# SH2_-_CONNECTORS.net
KiCad netlist of a schematic drawn in Altium Designer
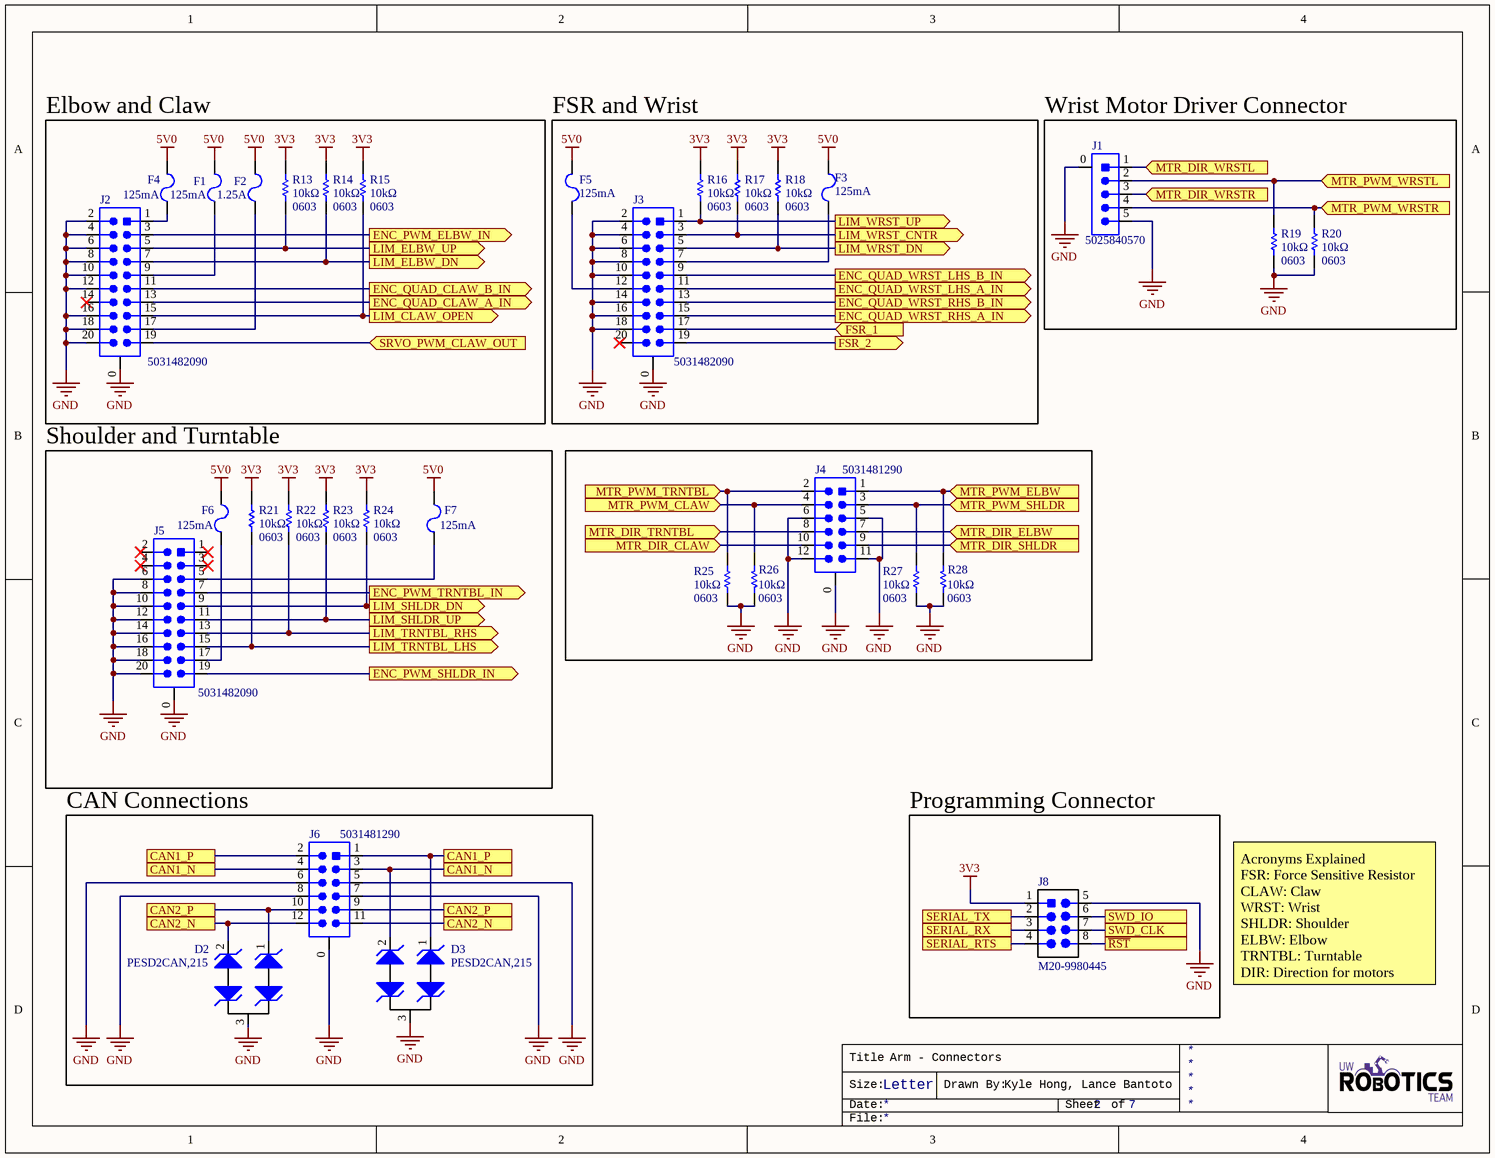
[diagram p0: SH2 - CONNECTORS.SchDoc]

(export (version "E")
  (design (tool "Eeschema 10.0.6"))
  (components
    (comp (ref "D2")
      (value "TVS_DIODE_CAN")
      (footprint "TVS_DIODE_CAN")
      (description "TVS DIODE 24V 41V SOT323-3")
      (fields (field (name "MANUFACTURER PART NUMBER 1") "PESD2CAN,215"))
      (libsource (lib "UWRT_Schematic_Library_2020") (part "TVS_DIODE_CAN"))
    )
    (comp (ref "D3")
      (value "TVS_DIODE_CAN")
      (footprint "TVS_DIODE_CAN")
      (description "TVS DIODE 24V 41V SOT323-3")
      (fields (field (name "MANUFACTURER PART NUMBER 1") "PESD2CAN,215"))
      (libsource (lib "UWRT_Schematic_Library_2020") (part "TVS_DIODE_CAN"))
    )
    (comp (ref "F1")
      (value "FUSE_125mA_1206")
      (footprint "FUSE_1206")
      (description "FUSE SMD 125mA 125V")
      (fields (field (name "CURRENT RATING") "125mA"))
      (libsource (lib "UWRT_Schematic_Library_2020") (part "FUSE_125mA_1206"))
    )
    (comp (ref "F2")
      (value "FUSE_1.25A_1206")
      (footprint "FUSE_1206")
      (description "FUSE SMD 1.25A 63V")
      (fields (field (name "CURRENT RATING") "1.25A"))
      (libsource (lib "UWRT_Schematic_Library_2020") (part "FUSE_1.25A_1206"))
    )
    (comp (ref "F3")
      (value "FUSE_125mA_1206")
      (footprint "FUSE_1206")
      (description "FUSE SMD 125mA 125V")
      (fields (field (name "CURRENT RATING") "125mA"))
      (libsource (lib "UWRT_Schematic_Library_2020") (part "FUSE_125mA_1206"))
    )
    (comp (ref "F4")
      (value "FUSE_125mA_1206")
      (footprint "FUSE_1206")
      (description "FUSE SMD 125mA 125V")
      (fields (field (name "CURRENT RATING") "125mA"))
      (libsource (lib "UWRT_Schematic_Library_2020") (part "FUSE_125mA_1206"))
    )
    (comp (ref "F5")
      (value "FUSE_125mA_1206")
      (footprint "FUSE_1206")
      (description "FUSE SMD 125mA 125V")
      (fields (field (name "CURRENT RATING") "125mA"))
      (libsource (lib "") (part "FUSE_125mA_1206_1"))
    )
    (comp (ref "F6")
      (value "FUSE_125mA_1206")
      (footprint "FUSE_1206")
      (description "FUSE SMD 125mA 125V")
      (fields (field (name "CURRENT RATING") "125mA"))
      (libsource (lib "UWRT_Schematic_Library_2020") (part "FUSE_125mA_1206"))
    )
    (comp (ref "F7")
      (value "FUSE_125mA_1206")
      (footprint "FUSE_1206")
      (description "FUSE SMD 125mA 125V")
      (fields (field (name "CURRENT RATING") "125mA"))
      (libsource (lib "UWRT_Schematic_Library_2020") (part "FUSE_125mA_1206"))
    )
    (comp (ref "J1")
      (value "CON_5M_SM_VT")
      (footprint "MOLEX-5025840570")
      (description "CONN HEADER SMD VERTICAL 1.5MM PITCH")
      (fields (field (name "MANUFACTURER PART NUMBER 1") "5025840570"))
      (libsource (lib "UWRT_Schematic_Library_2020") (part "CON_5M_SM_VT"))
    )
    (comp (ref "J2")
      (value "CON_10x2M_SM_RA")
      (footprint "MOLEX-5031482090")
      (description "CONN HEADER SMD RIGHT ANGLE 1.5MM PITCH")
      (fields (field (name "MANUFACTURER PART NUMBER 1") "5031482090"))
      (libsource (lib "UWRT_Schematic_Library_2020") (part "CON_10x2M_SM_RA"))
    )
    (comp (ref "J3")
      (value "CON_10x2M_SM_RA")
      (footprint "MOLEX-5031482090")
      (description "CONN HEADER SMD RIGHT ANGLE 1.5MM PITCH")
      (fields (field (name "MANUFACTURER PART NUMBER 1") "5031482090"))
      (libsource (lib "UWRT_Schematic_Library_2020") (part "CON_10x2M_SM_RA"))
    )
    (comp (ref "J4")
      (value "CON_6x2M_SM_RA")
      (footprint "MOLEX-5031481290")
      (description "CONN HEADER SMD RIGHT ANGLE 1.5MM PITCH")
      (fields (field (name "MANUFACTURER PART NUMBER 1") "5031481290"))
      (libsource (lib "UWRT_Schematic_Library_2020") (part "CON_6x2M_SM_RA"))
    )
    (comp (ref "J5")
      (value "CON_10x2M_SM_RA")
      (footprint "MOLEX-5031482090")
      (description "CONN HEADER SMD RIGHT ANGLE 1.5MM PITCH")
      (fields (field (name "MANUFACTURER PART NUMBER 1") "5031482090"))
      (libsource (lib "UWRT_Schematic_Library_2020") (part "CON_10x2M_SM_RA"))
    )
    (comp (ref "J6")
      (value "CON_6x2M_SM_RA")
      (footprint "MOLEX-5031481290")
      (description "CONN HEADER SMD RIGHT ANGLE 1.5MM PITCH")
      (fields (field (name "MANUFACTURER PART NUMBER 1") "5031481290"))
      (libsource (lib "UWRT_Schematic_Library_2020") (part "CON_6x2M_SM_RA"))
    )
    (comp (ref "J8")
      (value "HEADER 4X2")
      (footprint "HEADER_2X4")
      (description "CONN HEADER VERT 8POS 2.54MM")
      (fields (field (name "MANUFACTURER PART NUMBER 1") "M20-9980445"))
      (libsource (lib "UWRT_Schematic_Library_2020") (part "HEADER 4X2"))
    )
    (comp (ref "R13")
      (value "10kΩ")
      (footprint "RESC0603(1608)_N")
      (description "RES SMD 10K OHM 5% 1/10W 0603")
      (fields
        (field (name "TOLERANCE") "5%")
        (field (name "CASE CODE (IMPERIAL)") "0603")
        (field (name "Comment") "RES_10kΩ_0603")
      )
      (libsource (lib "UWRT_Schematic_Library_2020") (part "RES_10kΩ_0603"))
    )
    (comp (ref "R14")
      (value "10kΩ")
      (footprint "RESC0603(1608)_N")
      (description "RES SMD 10K OHM 5% 1/10W 0603")
      (fields
        (field (name "TOLERANCE") "5%")
        (field (name "CASE CODE (IMPERIAL)") "0603")
        (field (name "Comment") "RES_10kΩ_0603")
      )
      (libsource (lib "UWRT_Schematic_Library_2020") (part "RES_10kΩ_0603"))
    )
    (comp (ref "R15")
      (value "10kΩ")
      (footprint "RESC0603(1608)_N")
      (description "RES SMD 10K OHM 5% 1/10W 0603")
      (fields
        (field (name "TOLERANCE") "5%")
        (field (name "CASE CODE (IMPERIAL)") "0603")
        (field (name "Comment") "RES_10kΩ_0603")
      )
      (libsource (lib "UWRT_Schematic_Library_2020") (part "RES_10kΩ_0603"))
    )
    (comp (ref "R16")
      (value "10kΩ")
      (footprint "RESC0603(1608)_N")
      (description "RES SMD 10K OHM 5% 1/10W 0603")
      (fields
        (field (name "TOLERANCE") "5%")
        (field (name "CASE CODE (IMPERIAL)") "0603")
        (field (name "Comment") "RES_10kΩ_0603")
      )
      (libsource (lib "UWRT_Schematic_Library_2020") (part "RES_10kΩ_0603"))
    )
    (comp (ref "R17")
      (value "10kΩ")
      (footprint "RESC0603(1608)_N")
      (description "RES SMD 10K OHM 5% 1/10W 0603")
      (fields
        (field (name "TOLERANCE") "5%")
        (field (name "CASE CODE (IMPERIAL)") "0603")
        (field (name "Comment") "RES_10kΩ_0603")
      )
      (libsource (lib "UWRT_Schematic_Library_2020") (part "RES_10kΩ_0603"))
    )
    (comp (ref "R18")
      (value "10kΩ")
      (footprint "RESC0603(1608)_N")
      (description "RES SMD 10K OHM 5% 1/10W 0603")
      (fields
        (field (name "TOLERANCE") "5%")
        (field (name "CASE CODE (IMPERIAL)") "0603")
        (field (name "Comment") "RES_10kΩ_0603")
      )
      (libsource (lib "UWRT_Schematic_Library_2020") (part "RES_10kΩ_0603"))
    )
    (comp (ref "R19")
      (value "10kΩ")
      (footprint "RESC0603(1608)_N")
      (description "RES SMD 10K OHM 5% 1/10W 0603")
      (fields
        (field (name "TOLERANCE") "5%")
        (field (name "CASE CODE (IMPERIAL)") "0603")
        (field (name "Comment") "RES_10kΩ_0603")
      )
      (libsource (lib "UWRT_Schematic_Library_2020") (part "RES_10kΩ_0603"))
    )
    (comp (ref "R20")
      (value "10kΩ")
      (footprint "RESC0603(1608)_N")
      (description "RES SMD 10K OHM 5% 1/10W 0603")
      (fields
        (field (name "TOLERANCE") "5%")
        (field (name "CASE CODE (IMPERIAL)") "0603")
        (field (name "Comment") "RES_10kΩ_0603")
      )
      (libsource (lib "UWRT_Schematic_Library_2020") (part "RES_10kΩ_0603"))
    )
    (comp (ref "R21")
      (value "10kΩ")
      (footprint "RESC0603(1608)_N")
      (description "RES SMD 10K OHM 5% 1/10W 0603")
      (fields
        (field (name "TOLERANCE") "5%")
        (field (name "CASE CODE (IMPERIAL)") "0603")
        (field (name "Comment") "RES_10kΩ_0603")
      )
      (libsource (lib "UWRT_Schematic_Library_2020") (part "RES_10kΩ_0603"))
    )
    (comp (ref "R22")
      (value "10kΩ")
      (footprint "RESC0603(1608)_N")
      (description "RES SMD 10K OHM 5% 1/10W 0603")
      (fields
        (field (name "TOLERANCE") "5%")
        (field (name "CASE CODE (IMPERIAL)") "0603")
        (field (name "Comment") "RES_10kΩ_0603")
      )
      (libsource (lib "UWRT_Schematic_Library_2020") (part "RES_10kΩ_0603"))
    )
    (comp (ref "R23")
      (value "10kΩ")
      (footprint "RESC0603(1608)_N")
      (description "RES SMD 10K OHM 5% 1/10W 0603")
      (fields
        (field (name "TOLERANCE") "5%")
        (field (name "CASE CODE (IMPERIAL)") "0603")
        (field (name "Comment") "RES_10kΩ_0603")
      )
      (libsource (lib "UWRT_Schematic_Library_2020") (part "RES_10kΩ_0603"))
    )
    (comp (ref "R24")
      (value "10kΩ")
      (footprint "RESC0603(1608)_N")
      (description "RES SMD 10K OHM 5% 1/10W 0603")
      (fields
        (field (name "TOLERANCE") "5%")
        (field (name "CASE CODE (IMPERIAL)") "0603")
        (field (name "Comment") "RES_10kΩ_0603")
      )
      (libsource (lib "UWRT_Schematic_Library_2020") (part "RES_10kΩ_0603"))
    )
    (comp (ref "R25")
      (value "10kΩ")
      (footprint "RESC0603(1608)_N")
      (description "RES SMD 10K OHM 5% 1/10W 0603")
      (fields
        (field (name "TOLERANCE") "5%")
        (field (name "CASE CODE (IMPERIAL)") "0603")
        (field (name "Comment") "RES_10kΩ_0603")
      )
      (libsource (lib "UWRT_Schematic_Library_2020") (part "RES_10kΩ_0603"))
    )
    (comp (ref "R26")
      (value "10kΩ")
      (footprint "RESC0603(1608)_N")
      (description "RES SMD 10K OHM 5% 1/10W 0603")
      (fields
        (field (name "TOLERANCE") "5%")
        (field (name "CASE CODE (IMPERIAL)") "0603")
        (field (name "Comment") "RES_10kΩ_0603")
      )
      (libsource (lib "UWRT_Schematic_Library_2020") (part "RES_10kΩ_0603"))
    )
    (comp (ref "R27")
      (value "10kΩ")
      (footprint "RESC0603(1608)_N")
      (description "RES SMD 10K OHM 5% 1/10W 0603")
      (fields
        (field (name "TOLERANCE") "5%")
        (field (name "CASE CODE (IMPERIAL)") "0603")
        (field (name "Comment") "RES_10kΩ_0603")
      )
      (libsource (lib "UWRT_Schematic_Library_2020") (part "RES_10kΩ_0603"))
    )
    (comp (ref "R28")
      (value "10kΩ")
      (footprint "RESC0603(1608)_N")
      (description "RES SMD 10K OHM 5% 1/10W 0603")
      (fields
        (field (name "TOLERANCE") "5%")
        (field (name "CASE CODE (IMPERIAL)") "0603")
        (field (name "Comment") "RES_10kΩ_0603")
      )
      (libsource (lib "UWRT_Schematic_Library_2020") (part "RES_10kΩ_0603"))
    )
  )
  (nets
    (net (code "1") (name "/CAN1_N") (class "Default")
      (node (ref "D3") (pin "2") (pinfunction "2_2") (pintype "passive"))
      (node (ref "J6") (pin "3") (pinfunction "3_3") (pintype "passive"))
      (node (ref "J6") (pin "4") (pinfunction "4_4") (pintype "passive"))
    )
    (net (code "2") (name "/CAN1_P") (class "Default")
      (node (ref "D3") (pin "1") (pinfunction "1_1") (pintype "passive"))
      (node (ref "J6") (pin "1") (pinfunction "1_1") (pintype "passive"))
      (node (ref "J6") (pin "2") (pinfunction "2_2") (pintype "passive"))
    )
    (net (code "3") (name "/CAN2_N") (class "Default")
      (node (ref "D2") (pin "2") (pinfunction "2_2") (pintype "passive"))
      (node (ref "J6") (pin "11") (pinfunction "11_11") (pintype "passive"))
      (node (ref "J6") (pin "12") (pinfunction "12_12") (pintype "passive"))
    )
    (net (code "4") (name "/CAN2_P") (class "Default")
      (node (ref "D2") (pin "1") (pinfunction "1_1") (pintype "passive"))
      (node (ref "J6") (pin "10") (pinfunction "10_10") (pintype "passive"))
      (node (ref "J6") (pin "9") (pinfunction "9_9") (pintype "passive"))
    )
    (net (code "5") (name "/ENC_PWM_ELBW_IN") (class "Default")
      (node (ref "J2") (pin "3") (pinfunction "3_3") (pintype "passive"))
    )
    (net (code "6") (name "/ENC_PWM_SHLDR_IN") (class "Default")
      (node (ref "J5") (pin "19") (pinfunction "19_19") (pintype "passive"))
    )
    (net (code "7") (name "/ENC_PWM_TRNTBL_IN") (class "Default")
      (node (ref "J5") (pin "7") (pinfunction "7_7") (pintype "passive"))
    )
    (net (code "8") (name "/ENC_QUAD_CLAW_A_IN") (class "Default")
      (node (ref "J2") (pin "13") (pinfunction "13_13") (pintype "passive"))
    )
    (net (code "9") (name "/ENC_QUAD_CLAW_B_IN") (class "Default")
      (node (ref "J2") (pin "11") (pinfunction "11_11") (pintype "passive"))
    )
    (net (code "10") (name "/ENC_QUAD_WRST_LHS_A_IN") (class "Default")
      (node (ref "J3") (pin "11") (pinfunction "11_11") (pintype "passive"))
    )
    (net (code "11") (name "/ENC_QUAD_WRST_LHS_B_IN") (class "Default")
      (node (ref "J3") (pin "9") (pinfunction "9_9") (pintype "passive"))
    )
    (net (code "12") (name "/ENC_QUAD_WRST_RHS_A_IN") (class "Default")
      (node (ref "J3") (pin "15") (pinfunction "15_15") (pintype "passive"))
    )
    (net (code "13") (name "/ENC_QUAD_WRST_RHS_B_IN") (class "Default")
      (node (ref "J3") (pin "13") (pinfunction "13_13") (pintype "passive"))
    )
    (net (code "14") (name "/FSR_1") (class "Default")
      (node (ref "J3") (pin "17") (pinfunction "17_17") (pintype "passive"))
    )
    (net (code "15") (name "/FSR_2") (class "Default")
      (node (ref "J3") (pin "19") (pinfunction "19_19") (pintype "passive"))
    )
    (net (code "16") (name "/LIM_CLAW_OPEN") (class "Default")
      (node (ref "J2") (pin "15") (pinfunction "15_15") (pintype "passive"))
      (node (ref "R15") (pin "1") (pinfunction "1_1") (pintype "passive"))
    )
    (net (code "17") (name "/LIM_ELBW_DN") (class "Default")
      (node (ref "J2") (pin "7") (pinfunction "7_7") (pintype "passive"))
      (node (ref "R14") (pin "1") (pinfunction "1_1") (pintype "passive"))
    )
    (net (code "18") (name "/LIM_ELBW_UP") (class "Default")
      (node (ref "J2") (pin "5") (pinfunction "5_5") (pintype "passive"))
      (node (ref "R13") (pin "1") (pinfunction "1_1") (pintype "passive"))
    )
    (net (code "19") (name "/LIM_SHLDR_DN") (class "Default")
      (node (ref "J5") (pin "9") (pinfunction "9_9") (pintype "passive"))
      (node (ref "R24") (pin "1") (pinfunction "1_1") (pintype "passive"))
    )
    (net (code "20") (name "/LIM_SHLDR_UP") (class "Default")
      (node (ref "J5") (pin "11") (pinfunction "11_11") (pintype "passive"))
      (node (ref "R23") (pin "1") (pinfunction "1_1") (pintype "passive"))
    )
    (net (code "21") (name "/LIM_TRNTBL_LHS") (class "Default")
      (node (ref "J5") (pin "15") (pinfunction "15_15") (pintype "passive"))
      (node (ref "R21") (pin "1") (pinfunction "1_1") (pintype "passive"))
    )
    (net (code "22") (name "/LIM_TRNTBL_RHS") (class "Default")
      (node (ref "J5") (pin "13") (pinfunction "13_13") (pintype "passive"))
      (node (ref "R22") (pin "1") (pinfunction "1_1") (pintype "passive"))
    )
    (net (code "23") (name "/LIM_WRST_CNTR") (class "Default")
      (node (ref "J3") (pin "3") (pinfunction "3_3") (pintype "passive"))
      (node (ref "R17") (pin "1") (pinfunction "1_1") (pintype "passive"))
    )
    (net (code "24") (name "/LIM_WRST_DN") (class "Default")
      (node (ref "J3") (pin "5") (pinfunction "5_5") (pintype "passive"))
      (node (ref "R18") (pin "1") (pinfunction "1_1") (pintype "passive"))
    )
    (net (code "25") (name "/LIM_WRST_UP") (class "Default")
      (node (ref "J3") (pin "1") (pinfunction "1_1") (pintype "passive"))
      (node (ref "R16") (pin "1") (pinfunction "1_1") (pintype "passive"))
    )
    (net (code "26") (name "/MTR_DIR_CLAW") (class "Default")
      (node (ref "J4") (pin "10") (pinfunction "10_10") (pintype "passive"))
    )
    (net (code "27") (name "/MTR_DIR_ELBW") (class "Default")
      (node (ref "J4") (pin "7") (pinfunction "7_7") (pintype "passive"))
    )
    (net (code "28") (name "/MTR_DIR_SHLDR") (class "Default")
      (node (ref "J4") (pin "9") (pinfunction "9_9") (pintype "passive"))
    )
    (net (code "29") (name "/MTR_DIR_TRNTBL") (class "Default")
      (node (ref "J4") (pin "8") (pinfunction "8_8") (pintype "passive"))
    )
    (net (code "30") (name "/MTR_DIR_WRSTL") (class "Default")
      (node (ref "J1") (pin "1") (pinfunction "1_1") (pintype "passive"))
    )
    (net (code "31") (name "/MTR_DIR_WRSTR") (class "Default")
      (node (ref "J1") (pin "3") (pinfunction "3_3") (pintype "passive"))
    )
    (net (code "32") (name "/MTR_PWM_CLAW") (class "Default")
      (node (ref "J4") (pin "4") (pinfunction "4_4") (pintype "passive"))
      (node (ref "R26") (pin "2") (pinfunction "2_2") (pintype "passive"))
    )
    (net (code "33") (name "/MTR_PWM_ELBW") (class "Default")
      (node (ref "J4") (pin "1") (pinfunction "1_1") (pintype "passive"))
      (node (ref "R28") (pin "2") (pinfunction "2_2") (pintype "passive"))
    )
    (net (code "34") (name "/MTR_PWM_SHLDR") (class "Default")
      (node (ref "J4") (pin "3") (pinfunction "3_3") (pintype "passive"))
      (node (ref "R27") (pin "2") (pinfunction "2_2") (pintype "passive"))
    )
    (net (code "35") (name "/MTR_PWM_TRNTBL") (class "Default")
      (node (ref "J4") (pin "2") (pinfunction "2_2") (pintype "passive"))
      (node (ref "R25") (pin "2") (pinfunction "2_2") (pintype "passive"))
    )
    (net (code "36") (name "/MTR_PWM_WRSTL") (class "Default")
      (node (ref "J1") (pin "2") (pinfunction "2_2") (pintype "passive"))
      (node (ref "R19") (pin "2") (pinfunction "2_2") (pintype "passive"))
    )
    (net (code "37") (name "/MTR_PWM_WRSTR") (class "Default")
      (node (ref "J1") (pin "4") (pinfunction "4_4") (pintype "passive"))
      (node (ref "R20") (pin "2") (pinfunction "2_2") (pintype "passive"))
    )
    (net (code "38") (name "/SERIAL_RTS") (class "Default")
      (node (ref "J8") (pin "4") (pinfunction "4_4") (pintype "passive"))
    )
    (net (code "39") (name "/SERIAL_RX") (class "Default")
      (node (ref "J8") (pin "3") (pinfunction "3_3") (pintype "passive"))
    )
    (net (code "40") (name "/SERIAL_TX") (class "Default")
      (node (ref "J8") (pin "2") (pinfunction "2_2") (pintype "passive"))
    )
    (net (code "41") (name "/SRVO_PWM_CLAW_OUT") (class "Default")
      (node (ref "J2") (pin "19") (pinfunction "19_19") (pintype "passive"))
    )
    (net (code "42") (name "/SWD_CLK") (class "Default")
      (node (ref "J8") (pin "7") (pinfunction "3_7") (pintype "passive"))
    )
    (net (code "43") (name "/SWD_IO") (class "Default")
      (node (ref "J8") (pin "6") (pinfunction "2_6") (pintype "passive"))
    )
    (net (code "44") (name "/~{RST}") (class "Default")
      (node (ref "J8") (pin "8") (pinfunction "4_8") (pintype "passive"))
    )
    (net (code "45") (name "3V3") (class "Default")
      (node (ref "J8") (pin "1") (pinfunction "VCC_1") (pintype "passive"))
      (node (ref "R13") (pin "2") (pinfunction "2_2") (pintype "passive"))
      (node (ref "R14") (pin "2") (pinfunction "2_2") (pintype "passive"))
      (node (ref "R15") (pin "2") (pinfunction "2_2") (pintype "passive"))
      (node (ref "R16") (pin "2") (pinfunction "2_2") (pintype "passive"))
      (node (ref "R17") (pin "2") (pinfunction "2_2") (pintype "passive"))
      (node (ref "R18") (pin "2") (pinfunction "2_2") (pintype "passive"))
      (node (ref "R21") (pin "2") (pinfunction "2_2") (pintype "passive"))
      (node (ref "R22") (pin "2") (pinfunction "2_2") (pintype "passive"))
      (node (ref "R23") (pin "2") (pinfunction "2_2") (pintype "passive"))
      (node (ref "R24") (pin "2") (pinfunction "2_2") (pintype "passive"))
    )
    (net (code "46") (name "5V0") (class "Default")
      (node (ref "F1") (pin "2") (pinfunction "2_2") (pintype "passive"))
      (node (ref "F2") (pin "2") (pinfunction "2_2") (pintype "passive"))
      (node (ref "F3") (pin "2") (pinfunction "2_2") (pintype "passive"))
      (node (ref "F4") (pin "2") (pinfunction "2_2") (pintype "passive"))
      (node (ref "F5") (pin "2") (pinfunction "2_2") (pintype "passive"))
      (node (ref "F6") (pin "2") (pinfunction "2_2") (pintype "passive"))
      (node (ref "F7") (pin "2") (pinfunction "2_2") (pintype "passive"))
    )
    (net (code "47") (name "GND") (class "Default")
      (node (ref "D2") (pin "3") (pinfunction "3_3") (pintype "passive"))
      (node (ref "D3") (pin "3") (pinfunction "3_3") (pintype "passive"))
      (node (ref "J1") (pin "0") (pinfunction "0_0") (pintype "passive"))
      (node (ref "J1") (pin "5") (pinfunction "5_5") (pintype "passive"))
      (node (ref "J2") (pin "0") (pinfunction "0_0") (pintype "passive"))
      (node (ref "J2") (pin "10") (pinfunction "10_10") (pintype "passive"))
      (node (ref "J2") (pin "12") (pinfunction "12_12") (pintype "passive"))
      (node (ref "J2") (pin "16") (pinfunction "16_16") (pintype "passive"))
      (node (ref "J2") (pin "18") (pinfunction "18_18") (pintype "passive"))
      (node (ref "J2") (pin "2") (pinfunction "2_2") (pintype "passive"))
      (node (ref "J2") (pin "20") (pinfunction "20_20") (pintype "passive"))
      (node (ref "J2") (pin "4") (pinfunction "4_4") (pintype "passive"))
      (node (ref "J2") (pin "6") (pinfunction "6_6") (pintype "passive"))
      (node (ref "J2") (pin "8") (pinfunction "8_8") (pintype "passive"))
      (node (ref "J3") (pin "0") (pinfunction "0_0") (pintype "passive"))
      (node (ref "J3") (pin "10") (pinfunction "10_10") (pintype "passive"))
      (node (ref "J3") (pin "14") (pinfunction "14_14") (pintype "passive"))
      (node (ref "J3") (pin "16") (pinfunction "16_16") (pintype "passive"))
      (node (ref "J3") (pin "18") (pinfunction "18_18") (pintype "passive"))
      (node (ref "J3") (pin "2") (pinfunction "2_2") (pintype "passive"))
      (node (ref "J3") (pin "4") (pinfunction "4_4") (pintype "passive"))
      (node (ref "J3") (pin "6") (pinfunction "6_6") (pintype "passive"))
      (node (ref "J3") (pin "8") (pinfunction "8_8") (pintype "passive"))
      (node (ref "J4") (pin "0") (pinfunction "0_0") (pintype "passive"))
      (node (ref "J4") (pin "11") (pinfunction "11_11") (pintype "passive"))
      (node (ref "J4") (pin "12") (pinfunction "12_12") (pintype "passive"))
      (node (ref "J4") (pin "5") (pinfunction "5_5") (pintype "passive"))
      (node (ref "J4") (pin "6") (pinfunction "6_6") (pintype "passive"))
      (node (ref "J5") (pin "0") (pinfunction "0_0") (pintype "passive"))
      (node (ref "J5") (pin "10") (pinfunction "10_10") (pintype "passive"))
      (node (ref "J5") (pin "12") (pinfunction "12_12") (pintype "passive"))
      (node (ref "J5") (pin "14") (pinfunction "14_14") (pintype "passive"))
      (node (ref "J5") (pin "16") (pinfunction "16_16") (pintype "passive"))
      (node (ref "J5") (pin "18") (pinfunction "18_18") (pintype "passive"))
      (node (ref "J5") (pin "20") (pinfunction "20_20") (pintype "passive"))
      (node (ref "J5") (pin "6") (pinfunction "6_6") (pintype "passive"))
      (node (ref "J5") (pin "8") (pinfunction "8_8") (pintype "passive"))
      (node (ref "J6") (pin "0") (pinfunction "0_0") (pintype "passive"))
      (node (ref "J6") (pin "5") (pinfunction "5_5") (pintype "passive"))
      (node (ref "J6") (pin "6") (pinfunction "6_6") (pintype "passive"))
      (node (ref "J6") (pin "7") (pinfunction "7_7") (pintype "passive"))
      (node (ref "J6") (pin "8") (pinfunction "8_8") (pintype "passive"))
      (node (ref "J8") (pin "5") (pinfunction "GND_5") (pintype "passive"))
      (node (ref "R19") (pin "1") (pinfunction "1_1") (pintype "passive"))
      (node (ref "R20") (pin "1") (pinfunction "1_1") (pintype "passive"))
      (node (ref "R25") (pin "1") (pinfunction "1_1") (pintype "passive"))
      (node (ref "R26") (pin "1") (pinfunction "1_1") (pintype "passive"))
      (node (ref "R27") (pin "1") (pinfunction "1_1") (pintype "passive"))
      (node (ref "R28") (pin "1") (pinfunction "1_1") (pintype "passive"))
    )
    (net (code "48") (name "Net-(F1-Pad1)") (class "Default")
      (node (ref "F1") (pin "1") (pinfunction "1_1") (pintype "passive"))
      (node (ref "J2") (pin "9") (pinfunction "9_9") (pintype "passive"))
    )
    (net (code "49") (name "Net-(F2-Pad1)") (class "Default")
      (node (ref "F2") (pin "1") (pinfunction "1_1") (pintype "passive"))
      (node (ref "J2") (pin "17") (pinfunction "17_17") (pintype "passive"))
    )
    (net (code "50") (name "Net-(F3-Pad1)") (class "Default")
      (node (ref "F3") (pin "1") (pinfunction "1_1") (pintype "passive"))
      (node (ref "J3") (pin "7") (pinfunction "7_7") (pintype "passive"))
    )
    (net (code "51") (name "Net-(F4-Pad1)") (class "Default")
      (node (ref "F4") (pin "1") (pinfunction "1_1") (pintype "passive"))
      (node (ref "J2") (pin "1") (pinfunction "1_1") (pintype "passive"))
    )
    (net (code "52") (name "Net-(F5-Pad1)") (class "Default")
      (node (ref "F5") (pin "1") (pinfunction "1_1") (pintype "passive"))
      (node (ref "J3") (pin "12") (pinfunction "12_12") (pintype "passive"))
    )
    (net (code "53") (name "Net-(F6-Pad1)") (class "Default")
      (node (ref "F6") (pin "1") (pinfunction "1_1") (pintype "passive"))
      (node (ref "J5") (pin "17") (pinfunction "17_17") (pintype "passive"))
    )
    (net (code "54") (name "Net-(F7-Pad1)") (class "Default")
      (node (ref "F7") (pin "1") (pinfunction "1_1") (pintype "passive"))
      (node (ref "J5") (pin "5") (pinfunction "5_5") (pintype "passive"))
    )
    (net (code "55") (name "unconnected-(J2-Pad14)") (class "Default")
      (node (ref "J2") (pin "14") (pinfunction "14_14") (pintype "passive+no_connect"))
    )
    (net (code "56") (name "unconnected-(J3-Pad20)") (class "Default")
      (node (ref "J3") (pin "20") (pinfunction "20_20") (pintype "passive+no_connect"))
    )
    (net (code "57") (name "unconnected-(J5-Pad1)") (class "Default")
      (node (ref "J5") (pin "1") (pinfunction "1_1") (pintype "passive+no_connect"))
    )
    (net (code "58") (name "unconnected-(J5-Pad2)") (class "Default")
      (node (ref "J5") (pin "2") (pinfunction "2_2") (pintype "passive+no_connect"))
    )
    (net (code "59") (name "unconnected-(J5-Pad3)") (class "Default")
      (node (ref "J5") (pin "3") (pinfunction "3_3") (pintype "passive+no_connect"))
    )
    (net (code "60") (name "unconnected-(J5-Pad4)") (class "Default")
      (node (ref "J5") (pin "4") (pinfunction "4_4") (pintype "passive+no_connect"))
    )
  )
)
